# ControleM.net
KiCad netlist of a schematic drawn in EAGLE
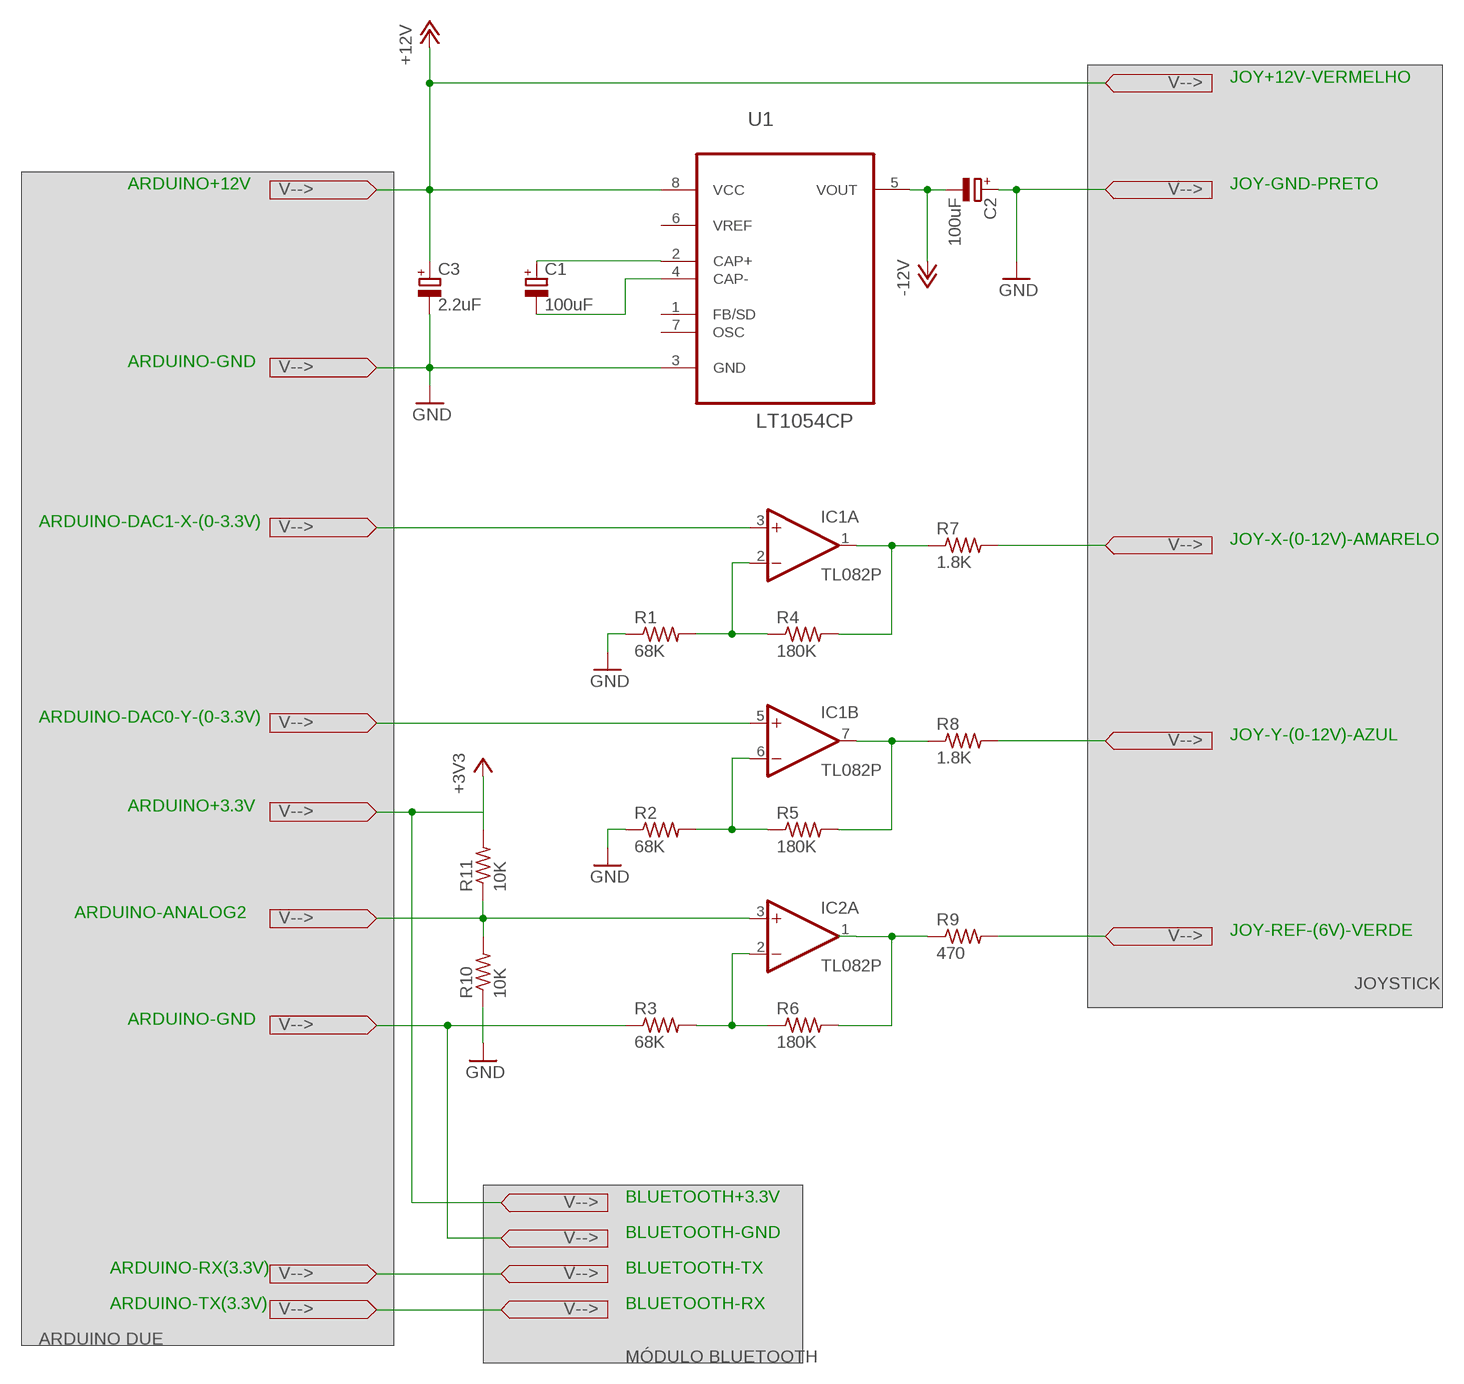
[diagram p0: schematic, sheet 1]

(export (version "E")
  (design (tool "Eeschema 10.0.6"))
  (components
    (comp (ref "C1")
      (value "100uF")
      (footprint "eagle-import:E2,5-6")
      (libsource (lib "eagle-import") (part "CPOL-EUE2.5-6"))
    )
    (comp (ref "C2")
      (value "100uF")
      (footprint "eagle-import:E2,5-6")
      (libsource (lib "eagle-import") (part "CPOL-EUE2.5-6"))
    )
    (comp (ref "C3")
      (value "2.2uF")
      (footprint "eagle-import:E2,5-6")
      (libsource (lib "eagle-import") (part "CPOL-EUE2.5-6"))
    )
    (comp (ref "IC1")
      (value "TL082P")
      (footprint "eagle-import:DIL08")
      (libsource (lib "eagle-import") (part "TL082P"))
    )
    (comp (ref "IC2")
      (value "TL082P")
      (footprint "eagle-import:DIL08")
      (libsource (lib "eagle-import") (part "TL082P"))
    )
    (comp (ref "R1")
      (value "68K")
      (footprint "eagle-import:0207_12")
      (libsource (lib "eagle-import") (part "R-US_0207/12"))
    )
    (comp (ref "R2")
      (value "68K")
      (footprint "eagle-import:0207_12")
      (libsource (lib "eagle-import") (part "R-US_0207/12"))
    )
    (comp (ref "R3")
      (value "68K")
      (footprint "eagle-import:0207_12")
      (libsource (lib "eagle-import") (part "R-US_0207/12"))
    )
    (comp (ref "R4")
      (value "180K")
      (footprint "eagle-import:0207_12")
      (libsource (lib "eagle-import") (part "R-US_0207/12"))
    )
    (comp (ref "R5")
      (value "180K")
      (footprint "eagle-import:0207_12")
      (libsource (lib "eagle-import") (part "R-US_0207/12"))
    )
    (comp (ref "R6")
      (value "180K")
      (footprint "eagle-import:0207_12")
      (libsource (lib "eagle-import") (part "R-US_0207/12"))
    )
    (comp (ref "R7")
      (value "1.8K")
      (footprint "eagle-import:0207_12")
      (libsource (lib "eagle-import") (part "R-US_0207/12"))
    )
    (comp (ref "R8")
      (value "1.8K")
      (footprint "eagle-import:0207_12")
      (libsource (lib "eagle-import") (part "R-US_0207/12"))
    )
    (comp (ref "R9")
      (value "470")
      (footprint "eagle-import:0207_12")
      (libsource (lib "eagle-import") (part "R-US_0207/12"))
    )
    (comp (ref "R10")
      (value "10K")
      (footprint "eagle-import:0207_12")
      (libsource (lib "eagle-import") (part "R-US_0207/12"))
    )
    (comp (ref "R11")
      (value "10K")
      (footprint "eagle-import:0207_12")
      (libsource (lib "eagle-import") (part "R-US_0207/12"))
    )
    (comp (ref "U1")
      (value "LT1054CP")
      (footprint "eagle-import:DIP254P762X508-8")
      (libsource (lib "eagle-import") (part "LT1054CP"))
    )
  )
  (nets
    (net (code "1") (name "+3V3") (class "Default")
      (node (ref "R11") (pin "2") (pinfunction "2_2") (pintype "passive"))
    )
    (net (code "2") (name "+12V") (class "Default")
      (node (ref "C3") (pin "+") (pinfunction "+_+") (pintype "passive"))
      (node (ref "U1") (pin "8") (pinfunction "VCC_8") (pintype "power_in"))
    )
    (net (code "3") (name "-12V") (class "Default")
      (node (ref "C2") (pin "-") (pinfunction "-_-") (pintype "passive"))
      (node (ref "U1") (pin "5") (pinfunction "VOUT_5") (pintype "output"))
    )
    (net (code "4") (name "GND") (class "Default")
      (node (ref "C2") (pin "+") (pinfunction "+_+") (pintype "passive"))
      (node (ref "C3") (pin "-") (pinfunction "-_-") (pintype "passive"))
      (node (ref "R1") (pin "1") (pinfunction "1_1") (pintype "passive"))
      (node (ref "R10") (pin "1") (pinfunction "1_1") (pintype "passive"))
      (node (ref "R2") (pin "1") (pinfunction "1_1") (pintype "passive"))
      (node (ref "R3") (pin "1") (pinfunction "1_1") (pintype "passive"))
      (node (ref "U1") (pin "3") (pinfunction "GND_3") (pintype "passive"))
    )
    (net (code "5") (name "Net-(IC1A--IN)") (class "Default")
      (node (ref "IC1") (pin "2") (pinfunction "-IN_2") (pintype "input"))
      (node (ref "R1") (pin "2") (pinfunction "2_2") (pintype "passive"))
      (node (ref "R4") (pin "1") (pinfunction "1_1") (pintype "passive"))
    )
    (net (code "6") (name "Net-(IC1A-OUT)") (class "Default")
      (node (ref "IC1") (pin "1") (pinfunction "OUT_1") (pintype "output"))
      (node (ref "R4") (pin "2") (pinfunction "2_2") (pintype "passive"))
      (node (ref "R7") (pin "1") (pinfunction "1_1") (pintype "passive"))
    )
    (net (code "7") (name "Net-(IC1B--IN)") (class "Default")
      (node (ref "IC1") (pin "6") (pinfunction "-IN_6") (pintype "input"))
      (node (ref "R2") (pin "2") (pinfunction "2_2") (pintype "passive"))
      (node (ref "R5") (pin "1") (pinfunction "1_1") (pintype "passive"))
    )
    (net (code "8") (name "Net-(IC1B-OUT)") (class "Default")
      (node (ref "IC1") (pin "7") (pinfunction "OUT_7") (pintype "output"))
      (node (ref "R5") (pin "2") (pinfunction "2_2") (pintype "passive"))
      (node (ref "R8") (pin "1") (pinfunction "1_1") (pintype "passive"))
    )
    (net (code "9") (name "Net-(IC2A-+IN)") (class "Default")
      (node (ref "IC2") (pin "3") (pinfunction "+IN_3") (pintype "input"))
      (node (ref "R10") (pin "2") (pinfunction "2_2") (pintype "passive"))
      (node (ref "R11") (pin "1") (pinfunction "1_1") (pintype "passive"))
    )
    (net (code "10") (name "Net-(IC2A--IN)") (class "Default")
      (node (ref "IC2") (pin "2") (pinfunction "-IN_2") (pintype "input"))
      (node (ref "R3") (pin "2") (pinfunction "2_2") (pintype "passive"))
      (node (ref "R6") (pin "1") (pinfunction "1_1") (pintype "passive"))
    )
    (net (code "11") (name "Net-(IC2A-OUT)") (class "Default")
      (node (ref "IC2") (pin "1") (pinfunction "OUT_1") (pintype "output"))
      (node (ref "R6") (pin "2") (pinfunction "2_2") (pintype "passive"))
      (node (ref "R9") (pin "1") (pinfunction "1_1") (pintype "passive"))
    )
    (net (code "12") (name "Net-(U1-CAP+)") (class "Default")
      (node (ref "C1") (pin "+") (pinfunction "+_+") (pintype "passive"))
      (node (ref "U1") (pin "2") (pinfunction "CAP+_2") (pintype "input"))
    )
    (net (code "13") (name "Net-(U1-CAP-)") (class "Default")
      (node (ref "C1") (pin "-") (pinfunction "-_-") (pintype "passive"))
      (node (ref "U1") (pin "4") (pinfunction "CAP-_4") (pintype "input"))
    )
    (net (code "14") (name "unconnected-(IC1A-+IN-Pad3)") (class "Default")
      (node (ref "IC1") (pin "3") (pinfunction "+IN_3") (pintype "input"))
    )
    (net (code "15") (name "unconnected-(IC1B-+IN-Pad5)") (class "Default")
      (node (ref "IC1") (pin "5") (pinfunction "+IN_5") (pintype "input"))
    )
    (net (code "16") (name "unconnected-(R7-Pad2)") (class "Default")
      (node (ref "R7") (pin "2") (pinfunction "2_2") (pintype "passive"))
    )
    (net (code "17") (name "unconnected-(R8-Pad2)") (class "Default")
      (node (ref "R8") (pin "2") (pinfunction "2_2") (pintype "passive"))
    )
    (net (code "18") (name "unconnected-(R9-Pad2)") (class "Default")
      (node (ref "R9") (pin "2") (pinfunction "2_2") (pintype "passive"))
    )
    (net (code "19") (name "unconnected-(U1-FB{slash}SD-Pad1)") (class "Default")
      (node (ref "U1") (pin "1") (pinfunction "FB/SD_1") (pintype "input"))
    )
    (net (code "20") (name "unconnected-(U1-OSC-Pad7)") (class "Default")
      (node (ref "U1") (pin "7") (pinfunction "OSC_7") (pintype "input"))
    )
    (net (code "21") (name "unconnected-(U1-VREF-Pad6)") (class "Default")
      (node (ref "U1") (pin "6") (pinfunction "VREF_6") (pintype "input"))
    )
  )
)
